# 15_Temp.net
KiCad netlist of a schematic drawn in Altium Designer
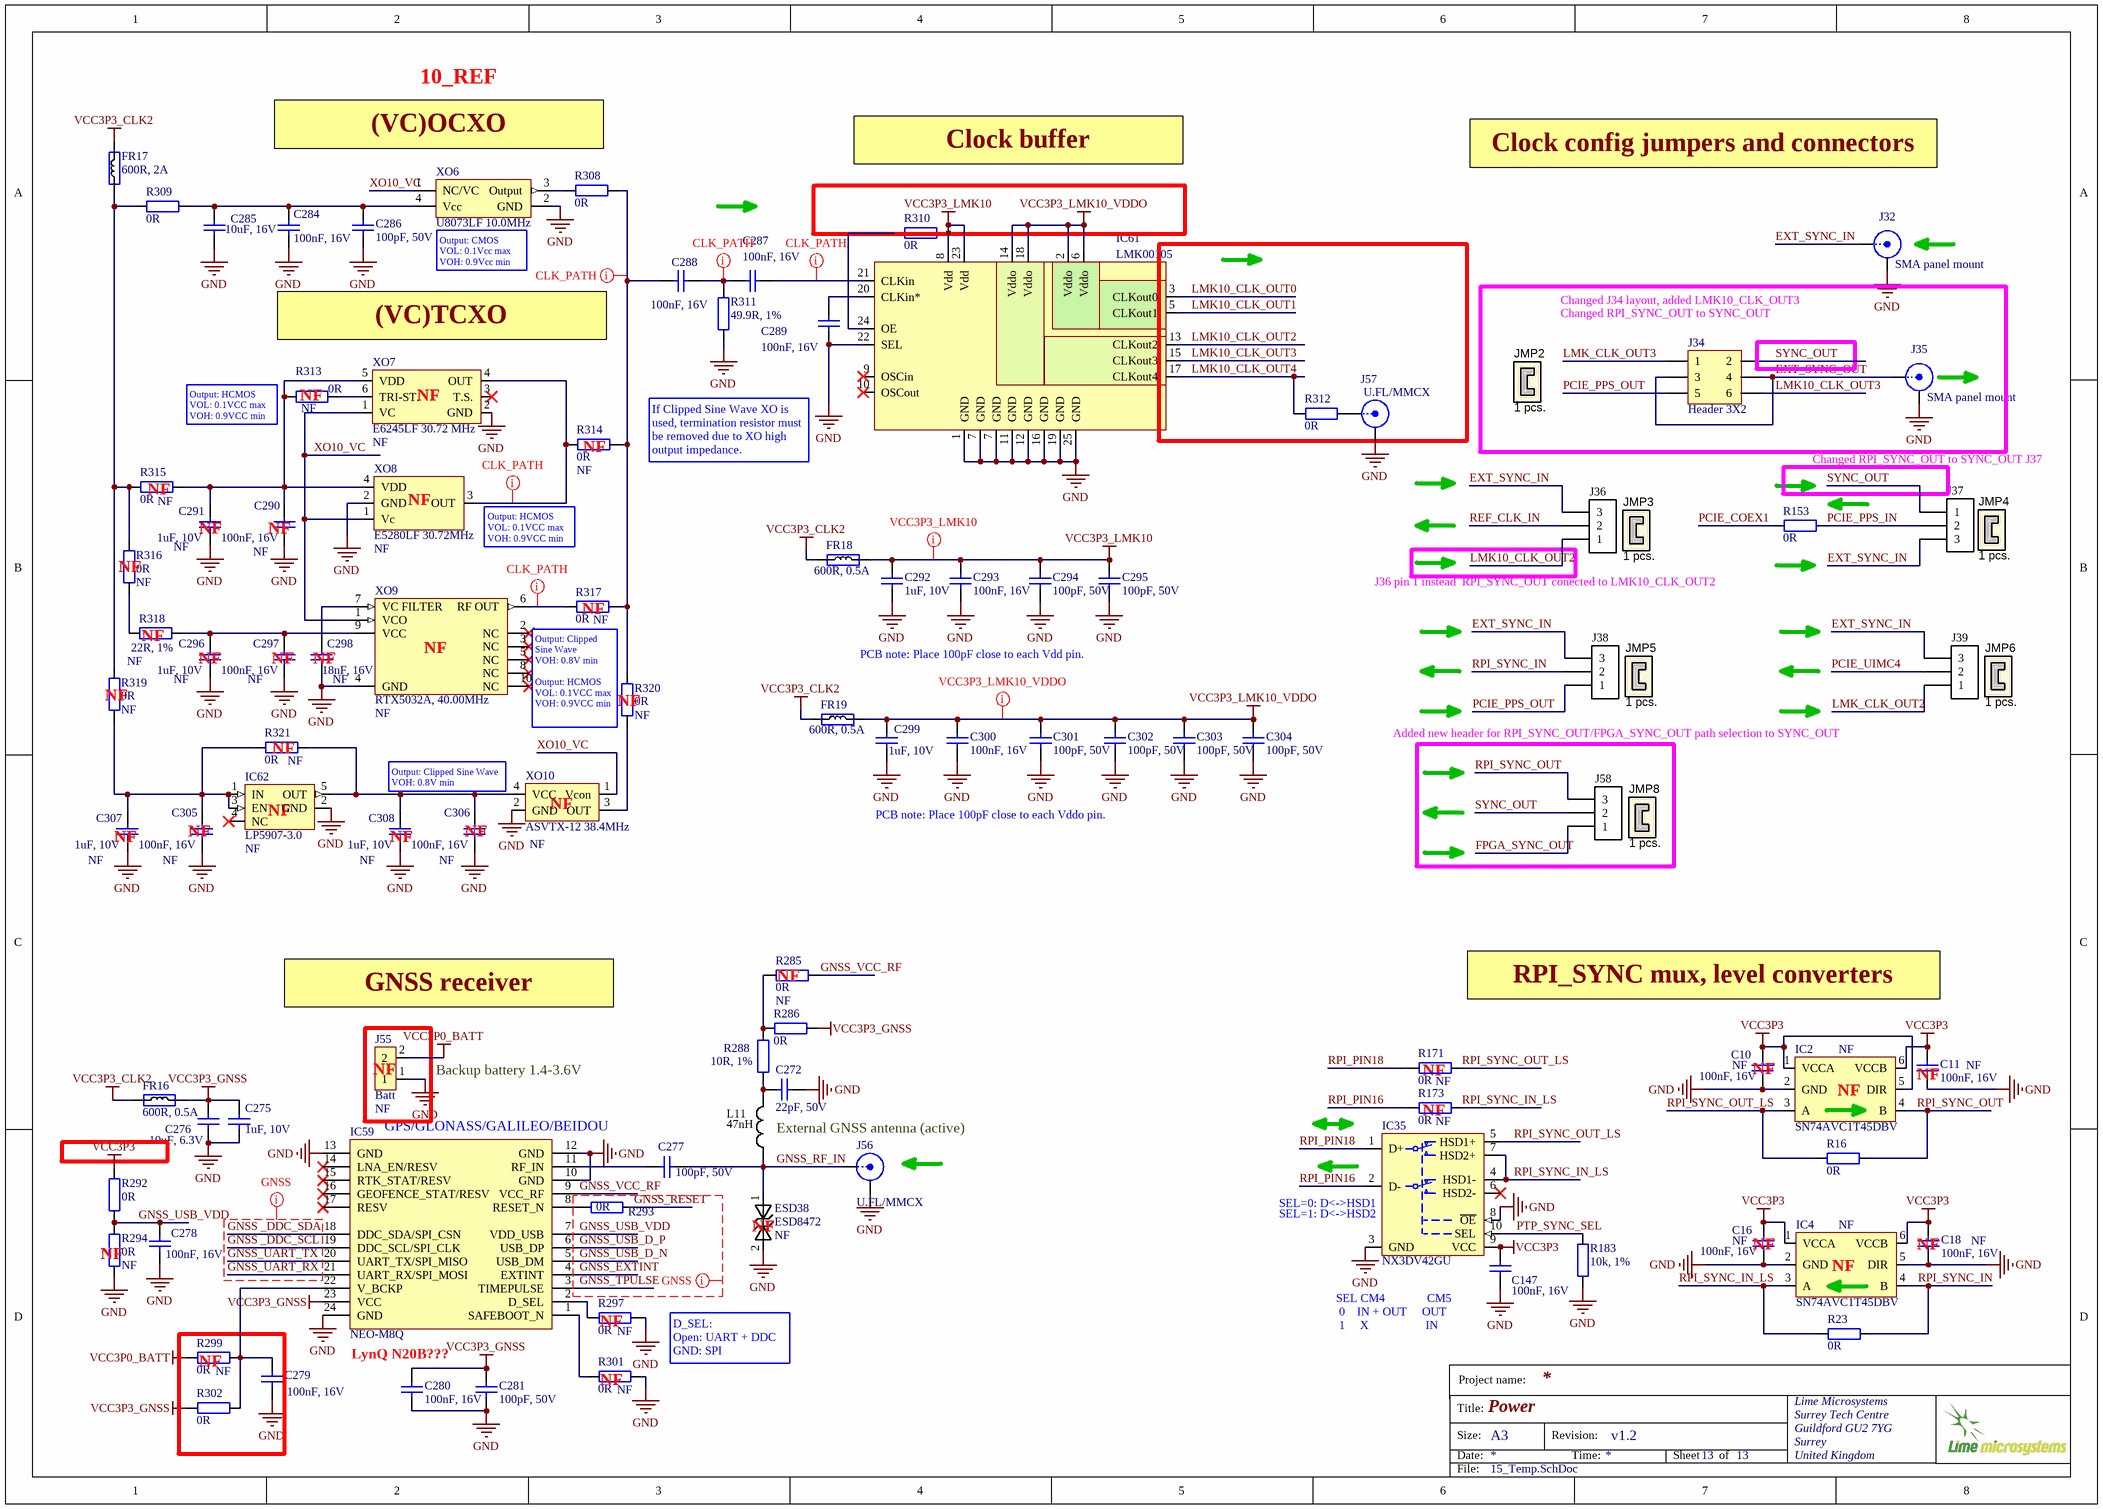
[diagram p0: 15_Temp.SchDoc]

(export (version "E")
  (design (tool "Eeschema 10.0.6"))
  (components
    (comp (ref "C10")
      (value "100nF, 16V")
      (footprint "CAP0402")
      (fields
        (field (name "ASSEMBLY INFO") "NF")
        (field (name "MANUFACTURER") "Murata Electronics")
        (field (name "TOLERANCE") "10 %")
        (field (name "MANUFACTURER PART NUMBER") "GRM155R71C104KA88D")
      )
      (libsource (lib "LimeMicroAltiumLib_schLib") (part "Cap_0402"))
    )
    (comp (ref "C11")
      (value "100nF, 16V")
      (footprint "CAP0402")
      (fields
        (field (name "ASSEMBLY INFO") "NF")
        (field (name "MANUFACTURER") "Murata Electronics")
        (field (name "TOLERANCE") "10 %")
        (field (name "MANUFACTURER PART NUMBER") "GRM155R71C104KA88D")
      )
      (libsource (lib "LimeMicroAltiumLib_schLib") (part "Cap_0402"))
    )
    (comp (ref "C16")
      (value "100nF, 16V")
      (footprint "CAP0402")
      (fields
        (field (name "ASSEMBLY INFO") "NF")
        (field (name "MANUFACTURER") "Murata Electronics")
        (field (name "TOLERANCE") "10 %")
        (field (name "MANUFACTURER PART NUMBER") "GRM155R71C104KA88D")
      )
      (libsource (lib "LimeMicroAltiumLib_schLib") (part "Cap_0402"))
    )
    (comp (ref "C18")
      (value "100nF, 16V")
      (footprint "CAP0402")
      (fields
        (field (name "ASSEMBLY INFO") "NF")
        (field (name "MANUFACTURER") "Murata Electronics")
        (field (name "TOLERANCE") "10 %")
        (field (name "MANUFACTURER PART NUMBER") "GRM155R71C104KA88D")
      )
      (libsource (lib "LimeMicroAltiumLib_schLib") (part "Cap_0402"))
    )
    (comp (ref "C147")
      (value "100nF, 16V")
      (footprint "CAP0402")
      (fields
        (field (name "MANUFACTURER") "Murata Electronics")
        (field (name "TOLERANCE") "10 %")
        (field (name "MANUFACTURER PART NUMBER") "GRM155R71C104KA88D")
      )
      (libsource (lib "LimeMicroAltiumLib_schLib") (part "Cap_0402"))
    )
    (comp (ref "C272")
      (value "22pF, 50V")
      (footprint "CAP0402")
      (fields (field (name "TOLERANCE") "±5%") (field (name "MANUFACTURER") "Yageo"))
      (libsource (lib "LimeMicroAltiumLib_schLib") (part "Cap_0402"))
    )
    (comp (ref "C275")
      (value "1uF, 10V")
      (footprint "CAP0402")
      (description "CAP CER 1UF 10V X5R 0402")
      (fields (field (name "MANUFACTURER") "TDK"))
      (libsource (lib "LimeMicroAltiumLib_schLib") (part "Cap_0402"))
    )
    (comp (ref "C276")
      (value "10uF, 6.3V")
      (footprint "CAP0603")
      (fields (field (name "TOLERANCE") "±20%") (field (name "MANUFACTURER") "Yageo"))
      (libsource (lib "LimeFPGAboard_schLib") (part "Cap_0603"))
    )
    (comp (ref "C277")
      (value "100pF, 50V")
      (footprint "CAP0402")
      (fields (field (name "TOLERANCE") "±5%") (field (name "MANUFACTURER") "Yageo"))
      (libsource (lib "LimeMicroAltiumLib_schLib") (part "Cap_0402"))
    )
    (comp (ref "C278")
      (value "100nF, 16V")
      (footprint "CAP0402")
      (fields
        (field (name "TOLERANCE") "10 %")
        (field (name "MANUFACTURER") "Murata Electronics")
        (field (name "MANUFACTURER PART NUMBER") "GRM155R71C104KA88D")
      )
      (libsource (lib "LimeFPGAboard_schLib") (part "Cap_0603"))
    )
    (comp (ref "C279")
      (value "100nF, 16V")
      (footprint "CAP0402")
      (fields
        (field (name "TOLERANCE") "10 %")
        (field (name "MANUFACTURER") "Murata Electronics")
        (field (name "MANUFACTURER PART NUMBER") "GRM155R71C104KA88D")
      )
      (libsource (lib "LimeFPGAboard_schLib") (part "Cap_0603"))
    )
    (comp (ref "C280")
      (value "100nF, 16V")
      (footprint "CAP0402")
      (fields
        (field (name "MANUFACTURER") "Murata Electronics")
        (field (name "TOLERANCE") "10 %")
        (field (name "MANUFACTURER PART NUMBER") "GRM155R71C104KA88D")
      )
      (libsource (lib "LimeMicroAltiumLib_schLib") (part "Cap_0402"))
    )
    (comp (ref "C281")
      (value "100pF, 50V")
      (footprint "CAP0402")
      (fields (field (name "TOLERANCE") "±5%") (field (name "MANUFACTURER") "Yageo"))
      (libsource (lib "LimeMicroAltiumLib_schLib") (part "Cap_0402"))
    )
    (comp (ref "C284")
      (value "100nF, 16V")
      (footprint "CAP0402")
      (fields
        (field (name "MANUFACTURER") "Murata Electronics")
        (field (name "TOLERANCE") "10 %")
        (field (name "MANUFACTURER PART NUMBER") "GRM155R71C104KA88D")
      )
      (libsource (lib "LimeMicroAltiumLib_schLib") (part "Cap_0402"))
    )
    (comp (ref "C285")
      (value "10uF, 16V")
      (footprint "CAP0603")
      (fields (field (name "MANUFACTURER") "Yageo") (field (name "TOLERANCE") "±20%"))
      (libsource (lib "LimeMicroAltiumLib_schLib") (part "Cap_0603"))
    )
    (comp (ref "C286")
      (value "100pF, 50V")
      (footprint "CAP0402")
      (fields (field (name "TOLERANCE") "±5%") (field (name "MANUFACTURER") "Yageo"))
      (libsource (lib "LimeMicroAltiumLib_schLib") (part "Cap_0402"))
    )
    (comp (ref "C287")
      (value "100nF, 16V")
      (footprint "CAP0402")
      (fields
        (field (name "MANUFACTURER") "Murata Electronics")
        (field (name "TOLERANCE") "10 %")
        (field (name "MANUFACTURER PART NUMBER") "GRM155R71C104KA88D")
      )
      (libsource (lib "LimeMicroAltiumLib_schLib") (part "Cap_0402"))
    )
    (comp (ref "C288")
      (value "100nF, 16V")
      (footprint "CAP0402")
      (fields
        (field (name "MANUFACTURER") "Murata Electronics")
        (field (name "TOLERANCE") "10 %")
        (field (name "MANUFACTURER PART NUMBER") "GRM155R71C104KA88D")
      )
      (libsource (lib "LimeMicroAltiumLib_schLib") (part "Cap_0402"))
    )
    (comp (ref "C289")
      (value "100nF, 16V")
      (footprint "CAP0402")
      (fields
        (field (name "MANUFACTURER") "Murata Electronics")
        (field (name "TOLERANCE") "10 %")
        (field (name "MANUFACTURER PART NUMBER") "GRM155R71C104KA88D")
      )
      (libsource (lib "LimeMicroAltiumLib_schLib") (part "Cap_0402"))
    )
    (comp (ref "C290")
      (value "100nF, 16V")
      (footprint "CAP0402")
      (fields
        (field (name "ASSEMBLY INFO") "NF")
        (field (name "MANUFACTURER") "Murata Electronics")
        (field (name "TOLERANCE") "10 %")
        (field (name "MANUFACTURER PART NUMBER") "GRM155R71C104KA88D")
      )
      (libsource (lib "LimeMicroAltiumLib_schLib") (part "Cap_0402"))
    )
    (comp (ref "C291")
      (value "1uF, 10V")
      (footprint "CAP0402")
      (description "CAP CER 1UF 10V X5R 0402")
      (fields (field (name "ASSEMBLY INFO") "NF") (field (name "MANUFACTURER") "Yageo"))
      (libsource (lib "LimeMicroAltiumLib_schLib") (part "Cap_0402"))
    )
    (comp (ref "C292")
      (value "1uF, 10V")
      (footprint "CAP0402")
      (description "CAP CER 1UF 10V X5R 0402")
      (fields (field (name "MANUFACTURER") "Yageo") (field (name "TOLERANCE") "±20%"))
      (libsource (lib "LimeMicroAltiumLib_schLib") (part "Cap_0402"))
    )
    (comp (ref "C293")
      (value "100nF, 16V")
      (footprint "CAP0402")
      (fields
        (field (name "MANUFACTURER") "Murata Electronics")
        (field (name "TOLERANCE") "10 %")
        (field (name "MANUFACTURER PART NUMBER") "GRM155R71C104KA88D")
      )
      (libsource (lib "LimeMicroAltiumLib_schLib") (part "Cap_0402"))
    )
    (comp (ref "C294")
      (value "100pF, 50V")
      (footprint "CAP0402")
      (fields (field (name "MANUFACTURER") "Yageo") (field (name "TOLERANCE") "±5%"))
      (libsource (lib "LimeMicroAltiumLib_schLib") (part "Cap_0402"))
    )
    (comp (ref "C295")
      (value "100pF, 50V")
      (footprint "CAP0402")
      (fields (field (name "MANUFACTURER") "Yageo") (field (name "TOLERANCE") "±5%"))
      (libsource (lib "LimeMicroAltiumLib_schLib") (part "Cap_0402"))
    )
    (comp (ref "C296")
      (value "1uF, 10V")
      (footprint "CAP0402")
      (description "CAP CER 1UF 10V X5R 0402")
      (fields (field (name "ASSEMBLY INFO") "NF") (field (name "MANUFACTURER") "Yageo"))
      (libsource (lib "LimeMicroAltiumLib_schLib") (part "Cap_0402"))
    )
    (comp (ref "C297")
      (value "100nF, 16V")
      (footprint "CAP0402")
      (fields
        (field (name "ASSEMBLY INFO") "NF")
        (field (name "MANUFACTURER") "Murata Electronics")
        (field (name "TOLERANCE") "10 %")
        (field (name "MANUFACTURER PART NUMBER") "GRM155R71C104KA88D")
      )
      (libsource (lib "LimeMicroAltiumLib_schLib") (part "Cap_0402"))
    )
    (comp (ref "C298")
      (value "18nF, 16V")
      (footprint "CAP0402")
      (fields
        (field (name "ASSEMBLY INFO") "NF")
        (field (name "MANUFACTURER") "Yageo")
        (field (name "TOLERANCE") "±10%")
      )
      (libsource (lib "LimeMicroAltiumLib_schLib") (part "Cap_0402"))
    )
    (comp (ref "C299")
      (value "1uF, 10V")
      (footprint "CAP0402")
      (description "CAP CER 1UF 10V X5R 0402")
      (fields (field (name "MANUFACTURER") "Yageo") (field (name "TOLERANCE") "±20%"))
      (libsource (lib "LimeMicroAltiumLib_schLib") (part "Cap_0402"))
    )
    (comp (ref "C300")
      (value "100nF, 16V")
      (footprint "CAP0402")
      (fields
        (field (name "MANUFACTURER") "Murata Electronics")
        (field (name "TOLERANCE") "10 %")
        (field (name "MANUFACTURER PART NUMBER") "GRM155R71C104KA88D")
      )
      (libsource (lib "LimeMicroAltiumLib_schLib") (part "Cap_0402"))
    )
    (comp (ref "C301")
      (value "100pF, 50V")
      (footprint "CAP0402")
      (fields (field (name "MANUFACTURER") "Yageo") (field (name "TOLERANCE") "±5%"))
      (libsource (lib "LimeMicroAltiumLib_schLib") (part "Cap_0402"))
    )
    (comp (ref "C302")
      (value "100pF, 50V")
      (footprint "CAP0402")
      (fields (field (name "MANUFACTURER") "Yageo") (field (name "TOLERANCE") "±5%"))
      (libsource (lib "LimeMicroAltiumLib_schLib") (part "Cap_0402"))
    )
    (comp (ref "C303")
      (value "100pF, 50V")
      (footprint "CAP0402")
      (fields (field (name "MANUFACTURER") "Yageo") (field (name "TOLERANCE") "±5%"))
      (libsource (lib "LimeMicroAltiumLib_schLib") (part "Cap_0402"))
    )
    (comp (ref "C304")
      (value "100pF, 50V")
      (footprint "CAP0402")
      (fields (field (name "MANUFACTURER") "Yageo") (field (name "TOLERANCE") "±5%"))
      (libsource (lib "LimeMicroAltiumLib_schLib") (part "Cap_0402"))
    )
    (comp (ref "C305")
      (value "100nF, 16V")
      (footprint "CAP0402")
      (fields
        (field (name "ASSEMBLY INFO") "NF")
        (field (name "MANUFACTURER") "Murata Electronics")
        (field (name "TOLERANCE") "10 %")
        (field (name "MANUFACTURER PART NUMBER") "GRM155R71C104KA88D")
      )
      (libsource (lib "") (part "Cap_0402_1"))
    )
    (comp (ref "C306")
      (value "100nF, 16V")
      (footprint "CAP0402")
      (fields
        (field (name "ASSEMBLY INFO") "NF")
        (field (name "MANUFACTURER") "Murata Electronics")
        (field (name "TOLERANCE") "10 %")
        (field (name "MANUFACTURER PART NUMBER") "GRM155R71C104KA88D")
      )
      (libsource (lib "") (part "Cap_0402_1"))
    )
    (comp (ref "C307")
      (value "1uF, 10V")
      (footprint "CAP0402")
      (fields (field (name "ASSEMBLY INFO") "NF") (field (name "MANUFACTURER") "Yageo"))
      (libsource (lib "") (part "Cap_0402_1"))
    )
    (comp (ref "C308")
      (value "1uF, 10V")
      (footprint "CAP0402")
      (fields (field (name "ASSEMBLY INFO") "NF") (field (name "MANUFACTURER") "Yageo"))
      (libsource (lib "") (part "Cap_0402_1"))
    )
    (comp (ref "ESD38")
      (value "ESD8472")
      (footprint "ESD8472_X3DFN2")
      (fields
        (field (name "MANUFACTURER") "ON Semiconductor")
        (field (name "MANUFACTURER PART NUMBER") "ESD8472MUT5G")
        (field (name "ASSEMBLY INFO") "NF")
      )
      (libsource (lib "LimeMicroAltiumLib_schLib") (part "ESD8472"))
    )
    (comp (ref "FR16")
      (value "600R, 0.5A")
      (footprint "RES0402")
      (fields
        (field (name "MANUFACTURER") "Murata")
        (field (name "TOLERANCE") "25%")
        (field (name "Comment") "Ferrite")
      )
      (libsource (lib "LimeMicroAltiumLib_schLib") (part "Ferrite"))
    )
    (comp (ref "FR17")
      (value "600R, 2A")
      (footprint "RES0805")
      (fields (field (name "MANUFACTURER") "TDK Corporation"))
      (libsource (lib "LimeFPGAboard_schLib") (part "Ferrite"))
    )
    (comp (ref "FR18")
      (value "600R, 0.5A")
      (footprint "RES0402")
      (fields (field (name "MANUFACTURER") "Murata") (field (name "TOLERANCE") "25%"))
      (libsource (lib "LimeMicroAltiumLib_schLib") (part "Ferrite"))
    )
    (comp (ref "FR19")
      (value "600R, 0.5A")
      (footprint "RES0402")
      (fields (field (name "MANUFACTURER") "Murata") (field (name "TOLERANCE") "25%"))
      (libsource (lib "LimeMicroAltiumLib_schLib") (part "Ferrite"))
    )
    (comp (ref "IC2")
      (value "SN74AVC1T45DBV")
      (footprint "SOT23-6")
      (fields (field (name "ASSEMBLY INFO") "NF") (field (name "MANUFACTURER") "Texas Instruments"))
      (libsource (lib "LimeMicroAltiumLib_schLib_r04") (part "SN74AVC1T45DBV"))
    )
    (comp (ref "IC4")
      (value "SN74AVC1T45DBV")
      (footprint "SOT23-6")
      (fields (field (name "ASSEMBLY INFO") "NF") (field (name "MANUFACTURER") "Texas Instruments"))
      (libsource (lib "LimeMicroAltiumLib_schLib_r04") (part "SN74AVC1T45DBV"))
    )
    (comp (ref "IC35")
      (value "NX3DV42GU")
      (footprint "FSUSB42UMX")
      (fields (field (name "MANUFACTURER") "NXP Semiconductors"))
      (libsource (lib "LimeMicroAltiumLib_schLib_r01") (part "FSUSB42UMX"))
    )
    (comp (ref "IC59")
      (value "NEO-M8Q")
      (footprint "NEO-7M/8M")
      (description "GNSS engine for GPS/QZSS, GLONASS")
      (fields (field (name "MANUFACTURER") "U-blox"))
      (libsource (lib "LimeMicroAltiumLib_schLib") (part "NEO-M8P_M8M"))
    )
    (comp (ref "IC61")
      (value "LMK00105")
      (footprint "LMK00105SQ")
      (fields (field (name "MANUFACTURER") "Texas Instruments"))
      (libsource (lib "LimeMicroAltiumLib_schLib") (part "LMK00105"))
    )
    (comp (ref "IC62")
      (value "LP5907-3.0")
      (footprint "SOT23-5")
      (fields (field (name "MANUFACTURER") "Texas Instruments") (field (name "ASSEMBLY INFO") "NF"))
      (libsource (lib "LimeMicroAltiumLib_schLib_r01") (part "LP5907"))
    )
    (comp (ref "J32")
      (value "SMA panel mount")
      (footprint "SMA_connector_side")
      (description "CONN SMA JACK STR 50OHM EDGE MNT")
      (fields (field (name "MANUFACTURER") "Linx"))
      (libsource (lib "LimeMicroAltiumLib_schLib") (part "RF_IF_connector"))
    )
    (comp (ref "J34")
      (value "Header 3X2")
      (footprint "Header3x2")
      (description "Header, 2-Pin, Dual row")
      (fields
        (field (name "MANUFACTURER PART NUMBER") "PH2-06-UA")
        (field (name "MANUFACTURER") "Adam Equipment")
      )
      (libsource (lib "LimeMicroAltiumLib_schLib_r01") (part "Header 3X2"))
    )
    (comp (ref "J35")
      (value "SMA panel mount")
      (footprint "SMA_connector_side")
      (description "CONN SMA JACK STR 50OHM EDGE MNT")
      (fields (field (name "MANUFACTURER") "Linx"))
      (libsource (lib "LimeMicroAltiumLib_schLib") (part "RF_IF_connector"))
    )
    (comp (ref "J36")
      (value "Header 3x1 pin")
      (footprint "HDR_1x3")
      (description "Header, 3-pin")
      (fields
        (field (name "MANUFACTURER PART NUMBER") "61300311121")
        (field (name "MANUFACTURER") "Wurth Electronics")
      )
      (libsource (lib "LimeMicroAltiumLib_schLib_r04") (part "Header3P"))
    )
    (comp (ref "J37")
      (value "Header 3x1 pin")
      (footprint "HDR_1x3")
      (description "Header, 3-pin")
      (fields
        (field (name "MANUFACTURER PART NUMBER") "61300311121")
        (field (name "MANUFACTURER") "Wurth Electronics")
      )
      (libsource (lib "") (part "Header3P_1"))
    )
    (comp (ref "J38")
      (value "Header 3x1 pin")
      (footprint "HDR_1x3")
      (description "Header, 3-pin")
      (fields
        (field (name "MANUFACTURER PART NUMBER") "61300311121")
        (field (name "MANUFACTURER") "Wurth Electronics")
      )
      (libsource (lib "LimeMicroAltiumLib_schLib_r04") (part "Header3P"))
    )
    (comp (ref "J39")
      (value "Header 3x1 pin")
      (footprint "HDR_1x3")
      (description "Header, 3-pin")
      (fields
        (field (name "MANUFACTURER PART NUMBER") "61300311121")
        (field (name "MANUFACTURER") "Wurth Electronics")
      )
      (libsource (lib "LimeMicroAltiumLib_schLib_r04") (part "Header3P"))
    )
    (comp (ref "J55")
      (value "Batt")
      (footprint "HDR_1x2")
      (fields (field (name "ASSEMBLY INFO") "NF") (field (name "MANUFACTURER") "3M"))
      (libsource (lib "LimeFPGAboard_schLib") (part "Jumper"))
    )
    (comp (ref "J56")
      (value "U.FL/MMCX")
      (footprint "MMCX_UFL_conn_u")
      (description "CONN UMC RCPT STR 50 OHM SMD")
      (fields (field (name "MANUFACTURER") "Molex, LLC"))
      (libsource (lib "") (part "RF_IF_connector_1"))
    )
    (comp (ref "J57")
      (value "U.FL/MMCX")
      (footprint "MMCX_UFL_conn_u")
      (description "CONN UMC RCPT STR 50 OHM SMD")
      (fields (field (name "MANUFACTURER") "Molex, LLC"))
      (libsource (lib "") (part "RF_IF_connector_1"))
    )
    (comp (ref "J58")
      (value "Header 3x1 pin")
      (footprint "HDR_1x3")
      (description "Header, 3-pin")
      (fields
        (field (name "MANUFACTURER PART NUMBER") "61300311121")
        (field (name "MANUFACTURER") "Wurth Electronics")
      )
      (libsource (lib "LimeMicroAltiumLib_schLib_r04") (part "Header3P"))
    )
    (comp (ref "JMP2")
      (value "1 pcs.")
      (description "Shorting Jumper, 2-position, 1.27mm pitch")
      (fields (field (name "MANUFACTURER") "Sullins"))
      (libsource (lib "LimeMicroAltiumLib_schLib") (part "JUMP_2P_CONN_HEADER"))
    )
    (comp (ref "JMP3")
      (value "1 pcs.")
      (description "Shorting Jumper, 2-position, 1.27mm pitch")
      (fields (field (name "MANUFACTURER") "Sullins"))
      (libsource (lib "LimeMicroAltiumLib_schLib") (part "JUMP_2P_CONN_HEADER"))
    )
    (comp (ref "JMP4")
      (value "1 pcs.")
      (description "Shorting Jumper, 2-position, 1.27mm pitch")
      (fields (field (name "MANUFACTURER") "Sullins"))
      (libsource (lib "LimeMicroAltiumLib_schLib") (part "JUMP_2P_CONN_HEADER"))
    )
    (comp (ref "JMP5")
      (value "1 pcs.")
      (description "Shorting Jumper, 2-position, 1.27mm pitch")
      (fields (field (name "MANUFACTURER") "Sullins"))
      (libsource (lib "LimeMicroAltiumLib_schLib") (part "JUMP_2P_CONN_HEADER"))
    )
    (comp (ref "JMP6")
      (value "1 pcs.")
      (description "Shorting Jumper, 2-position, 1.27mm pitch")
      (fields (field (name "MANUFACTURER") "Sullins"))
      (libsource (lib "LimeMicroAltiumLib_schLib") (part "JUMP_2P_CONN_HEADER"))
    )
    (comp (ref "JMP8")
      (value "1 pcs.")
      (description "Shorting Jumper, 2-position, 1.27mm pitch")
      (fields (field (name "MANUFACTURER") "Sullins"))
      (libsource (lib "LimeMicroAltiumLib_schLib") (part "JUMP_2P_CONN_HEADER"))
    )
    (comp (ref "L11")
      (value "47nH")
      (footprint "RES0402")
      (fields
        (field (name "MANUFACTURER") "COILCRAFT")
        (field (name "MANUFACTURER PART NUMBER") "0402HP-47NXJLU")
      )
      (libsource (lib "LimeMicroAltiumLib_schLib") (part "Inductor_0603"))
    )
    (comp (ref "R16")
      (value "0R")
      (footprint "RES0402")
      (fields (field (name "MANUFACTURER") "Yageo") (field (name "TOLERANCE") "Jumper"))
      (libsource (lib "LimeFPGAboard_schLib") (part "Res_0402"))
    )
    (comp (ref "R23")
      (value "0R")
      (footprint "RES0402")
      (fields (field (name "MANUFACTURER") "Yageo") (field (name "TOLERANCE") "Jumper"))
      (libsource (lib "LimeFPGAboard_schLib") (part "Res_0402"))
    )
    (comp (ref "R153")
      (value "0R")
      (footprint "RES0402")
      (fields (field (name "MANUFACTURER") "Yageo") (field (name "TOLERANCE") "Jumper"))
      (libsource (lib "") (part "Res_0402_1"))
    )
    (comp (ref "R171")
      (value "0R")
      (footprint "RES0402")
      (fields
        (field (name "ASSEMBLY INFO") "NF")
        (field (name "MANUFACTURER") "Yageo")
        (field (name "TOLERANCE") "Jumper")
      )
      (libsource (lib "") (part "Res_0402_1"))
    )
    (comp (ref "R173")
      (value "0R")
      (footprint "RES0402")
      (fields
        (field (name "ASSEMBLY INFO") "NF")
        (field (name "MANUFACTURER") "Yageo")
        (field (name "TOLERANCE") "Jumper")
      )
      (libsource (lib "") (part "Res_0402_1"))
    )
    (comp (ref "R183")
      (value "10k, 1%")
      (footprint "RES0402")
      (fields (field (name "MANUFACTURER") "Yageo") (field (name "TOLERANCE") "±1%"))
      (libsource (lib "LimeMicroAltiumLib_schLib") (part "Res_0402"))
    )
    (comp (ref "R285")
      (value "0R")
      (footprint "RES0402")
      (fields
        (field (name "ASSEMBLY INFO") "NF")
        (field (name "MANUFACTURER") "Yageo")
        (field (name "TOLERANCE") "Jumper")
      )
      (libsource (lib "LimeMicroAltiumLib_schLib") (part "Res_0402"))
    )
    (comp (ref "R286")
      (value "0R")
      (footprint "RES0402")
      (fields (field (name "MANUFACTURER") "Yageo") (field (name "TOLERANCE") "Jumper"))
      (libsource (lib "LimeMicroAltiumLib_schLib") (part "Res_0402"))
    )
    (comp (ref "R288")
      (value "10R, 1%")
      (footprint "RES0402")
      (fields (field (name "MANUFACTURER") "Stackpole Electronics") (field (name "TOLERANCE") "1%"))
      (libsource (lib "LimeMicroAltiumLib_schLib") (part "Res_0402"))
    )
    (comp (ref "R292")
      (value "0R")
      (footprint "RES0402")
      (fields (field (name "MANUFACTURER") "Yageo") (field (name "TOLERANCE") "Jumper"))
      (libsource (lib "LimeMicroAltiumLib_schLib") (part "Res_0402"))
    )
    (comp (ref "R293")
      (value "0R")
      (footprint "RES0402")
      (fields (field (name "MANUFACTURER") "Yageo") (field (name "TOLERANCE") "Jumper"))
      (libsource (lib "LimeMicroAltiumLib_schLib") (part "Res_0402"))
    )
    (comp (ref "R294")
      (value "0R")
      (footprint "RES0402")
      (fields
        (field (name "ASSEMBLY INFO") "NF")
        (field (name "MANUFACTURER") "Yageo")
        (field (name "TOLERANCE") "Jumper")
      )
      (libsource (lib "LimeMicroAltiumLib_schLib") (part "Res_0402"))
    )
    (comp (ref "R297")
      (value "0R")
      (footprint "RES0402")
      (fields
        (field (name "ASSEMBLY INFO") "NF")
        (field (name "MANUFACTURER") "Yageo")
        (field (name "TOLERANCE") "Jumper")
      )
      (libsource (lib "LimeMicroAltiumLib_schLib") (part "Res_0402"))
    )
    (comp (ref "R299")
      (value "0R")
      (footprint "RES0402")
      (fields
        (field (name "ASSEMBLY INFO") "NF")
        (field (name "MANUFACTURER") "Yageo")
        (field (name "TOLERANCE") "Jumper")
      )
      (libsource (lib "LimeMicroAltiumLib_schLib") (part "Res_0402"))
    )
    (comp (ref "R301")
      (value "0R")
      (footprint "RES0402")
      (fields
        (field (name "ASSEMBLY INFO") "NF")
        (field (name "MANUFACTURER") "Yageo")
        (field (name "TOLERANCE") "Jumper")
      )
      (libsource (lib "LimeMicroAltiumLib_schLib") (part "Res_0402"))
    )
    (comp (ref "R302")
      (value "0R")
      (footprint "RES0402")
      (fields (field (name "MANUFACTURER") "Yageo") (field (name "TOLERANCE") "Jumper"))
      (libsource (lib "LimeMicroAltiumLib_schLib") (part "Res_0402"))
    )
    (comp (ref "R308")
      (value "0R")
      (footprint "RES0402_v2")
      (fields (field (name "MANUFACTURER") "Yageo") (field (name "TOLERANCE") "Jumper"))
      (libsource (lib "LimeMicroAltiumLib_schLib") (part "Res_0402"))
    )
    (comp (ref "R309")
      (value "0R")
      (footprint "RES0402")
      (fields (field (name "MANUFACTURER") "Yageo") (field (name "TOLERANCE") "Jumper"))
      (libsource (lib "LimeMicroAltiumLib_schLib") (part "Res_0402"))
    )
    (comp (ref "R310")
      (value "0R")
      (footprint "RES0402")
      (fields (field (name "MANUFACTURER") "Yageo") (field (name "TOLERANCE") "Jumper"))
      (libsource (lib "LimeMicroAltiumLib_schLib") (part "Res_0402"))
    )
    (comp (ref "R311")
      (value "49.9R, 1%")
      (footprint "RES0402")
      (fields
        (field (name "TOLERANCE") "±1%")
        (field (name "MANUFACTURER") "Samsung Electro-Mechanics America, Inc.")
      )
      (libsource (lib "LimeMicroAltiumLib_schLib") (part "Res_0402"))
    )
    (comp (ref "R312")
      (value "0R")
      (footprint "RES0402")
      (fields (field (name "MANUFACTURER") "Yageo") (field (name "TOLERANCE") "Jumper"))
      (libsource (lib "") (part "Res_0402_1"))
    )
    (comp (ref "R313")
      (value "0R")
      (footprint "RES0402")
      (fields
        (field (name "ASSEMBLY INFO") "NF")
        (field (name "MANUFACTURER") "Yageo")
        (field (name "TOLERANCE") "Jumper")
      )
      (libsource (lib "LimeMicroAltiumLib_schLib") (part "Res_0402"))
    )
    (comp (ref "R314")
      (value "0R")
      (footprint "RES0402_v2")
      (fields
        (field (name "ASSEMBLY INFO") "NF")
        (field (name "MANUFACTURER") "Yageo")
        (field (name "TOLERANCE") "Jumper")
      )
      (libsource (lib "LimeMicroAltiumLib_schLib") (part "Res_0402"))
    )
    (comp (ref "R315")
      (value "0R")
      (footprint "RES0402")
      (fields
        (field (name "MANUFACTURER") "Yageo")
        (field (name "TOLERANCE") "Jumper")
        (field (name "ASSEMBLY INFO") "NF")
      )
      (libsource (lib "LimeMicroAltiumLib_schLib") (part "Res_0402"))
    )
    (comp (ref "R316")
      (value "0R")
      (footprint "RES0402")
      (fields
        (field (name "ASSEMBLY INFO") "NF")
        (field (name "MANUFACTURER") "Yageo")
        (field (name "TOLERANCE") "Jumper")
      )
      (libsource (lib "LimeMicroAltiumLib_schLib") (part "Res_0402"))
    )
    (comp (ref "R317")
      (value "0R")
      (footprint "RES0402_v2")
      (fields
        (field (name "ASSEMBLY INFO") "NF")
        (field (name "MANUFACTURER") "Yageo")
        (field (name "TOLERANCE") "Jumper")
      )
      (libsource (lib "LimeMicroAltiumLib_schLib") (part "Res_0402"))
    )
    (comp (ref "R318")
      (value "22R, 1%")
      (footprint "RES0402")
      (fields
        (field (name "TOLERANCE") "±1%")
        (field (name "MANUFACTURER") "Yageo")
        (field (name "ASSEMBLY INFO") "NF")
      )
      (libsource (lib "LimeFPGAboard_schLib") (part "Res_0402"))
    )
    (comp (ref "R319")
      (value "0R")
      (footprint "RES0402")
      (fields
        (field (name "MANUFACTURER") "Yageo")
        (field (name "TOLERANCE") "Jumper")
        (field (name "ASSEMBLY INFO") "NF")
      )
      (libsource (lib "") (part "Res_0402_1"))
    )
    (comp (ref "R320")
      (value "0R")
      (footprint "RES0402_v2")
      (fields
        (field (name "ASSEMBLY INFO") "NF")
        (field (name "MANUFACTURER") "Yageo")
        (field (name "TOLERANCE") "Jumper")
      )
      (libsource (lib "") (part "Res_0402_1"))
    )
    (comp (ref "R321")
      (value "0R")
      (footprint "RES0402")
      (fields
        (field (name "MANUFACTURER") "Yageo")
        (field (name "TOLERANCE") "Jumper")
        (field (name "ASSEMBLY INFO") "NF")
      )
      (libsource (lib "") (part "Res_0402_1"))
    )
    (comp (ref "XO6")
      (value "U8073LF 10.0MHz")
      (footprint "AOCJYR-10.000MHz")
      (fields (field (name "MANUFACTURER") "Rakon"))
      (libsource (lib "LimeMicroAltiumLib_schLib") (part "AOCJYR-10.000MHz"))
    )
    (comp (ref "XO7")
      (value "E6245LF 30.72 MHz")
      (footprint "RAKON_RPT7050A")
      (fields (field (name "ASSEMBLY INFO") "NF") (field (name "MANUFACTURER") "Rakon"))
      (libsource (lib "LimeMicroAltiumLib_schLib") (part "RPT7050A"))
    )
    (comp (ref "XO8")
      (value "E5280LF 30.72MHz")
      (footprint "RAKON_TXCO")
      (fields (field (name "ASSEMBLY INFO") "NF") (field (name "MANUFACTURER") "Rakon"))
      (libsource (lib "LimeMicroAltiumLib_schLib") (part "TXCO"))
    )
    (comp (ref "XO9")
      (value "RTX5032A, 40.00MHz")
      (footprint "RAKON_RTX5032A")
      (fields (field (name "ASSEMBLY INFO") "NF") (field (name "MANUFACTURER") "Rakon"))
      (libsource (lib "LimeMicroAltiumLib_schLib") (part "Rakon_RTX5032A"))
    )
    (comp (ref "XO10")
      (value "ASVTX-12 38.4MHz")
      (footprint "CRYSTAL_4-LCC_2P5x2P0")
      (description "Oscillator Crystal")
      (fields (field (name "MANUFACTURER") "Abracon") (field (name "ASSEMBLY INFO") "NF"))
      (libsource (lib "LimeMicroAltiumLib_schLib_r01") (part "ASVTX-12-A-38.400MHZ-H10-T_CRYSTAL"))
    )
  )
  (nets
    (net (code "1") (name "/EXT_SYNC_IN") (class "Default")
      (node (ref "J32") (pin "1") (pinfunction "X_1") (pintype "passive"))
      (node (ref "J36") (pin "3") (pinfunction "3_3") (pintype "passive"))
      (node (ref "J37") (pin "3") (pinfunction "3_3") (pintype "passive"))
      (node (ref "J38") (pin "3") (pinfunction "3_3") (pintype "passive"))
      (node (ref "J39") (pin "3") (pinfunction "3_3") (pintype "passive"))
    )
    (net (code "2") (name "/EXT_SYNC_OUT") (class "Default")
      (node (ref "J34") (pin "3") (pinfunction "3_3") (pintype "passive"))
      (node (ref "J34") (pin "4") (pinfunction "4_4") (pintype "passive"))
      (node (ref "J35") (pin "1") (pinfunction "X_1") (pintype "passive"))
    )
    (net (code "3") (name "/FPGA_SYNC_OUT") (class "Default")
      (node (ref "J58") (pin "1") (pinfunction "1_1") (pintype "passive"))
    )
    (net (code "4") (name "/GNSS _DDC_SCL") (class "Default")
      (node (ref "IC59") (pin "19") (pinfunction "DDC_SCL/SPI_CLK_19") (pintype "passive"))
    )
    (net (code "5") (name "/GNSS _DDC_SDA") (class "Default")
      (node (ref "IC59") (pin "18") (pinfunction "DDC_SDA/SPI_CSN_18") (pintype "passive"))
    )
    (net (code "6") (name "/GNSS_EXTINT") (class "Default")
      (node (ref "IC59") (pin "4") (pinfunction "EXTINT_4") (pintype "passive"))
    )
    (net (code "7") (name "/GNSS_RESET") (class "Default")
      (node (ref "R293") (pin "1") (pinfunction "1_1") (pintype "passive"))
    )
    (net (code "8") (name "/GNSS_RF_IN") (class "Default")
      (node (ref "C277") (pin "1") (pinfunction "1_1") (pintype "passive"))
      (node (ref "ESD38") (pin "1") (pinfunction "1_1") (pintype "passive"))
      (node (ref "J56") (pin "1") (pinfunction "X_1") (pintype "passive"))
      (node (ref "L11") (pin "1") (pinfunction "1_1") (pintype "passive"))
    )
    (net (code "9") (name "/GNSS_TPULSE") (class "Default")
      (node (ref "IC59") (pin "3") (pinfunction "TIMEPULSE_3") (pintype "passive"))
    )
    (net (code "10") (name "/GNSS_UART_RX") (class "Default")
      (node (ref "IC59") (pin "21") (pinfunction "UART_RX/SPI_MOSI_21") (pintype "passive"))
    )
    (net (code "11") (name "/GNSS_UART_TX") (class "Default")
      (node (ref "IC59") (pin "20") (pinfunction "UART_TX/SPI_MISO_20") (pintype "passive"))
    )
    (net (code "12") (name "/GNSS_USB_D_N") (class "Default")
      (node (ref "IC59") (pin "5") (pinfunction "USB_DM_5") (pintype "passive"))
    )
    (net (code "13") (name "/GNSS_USB_D_P") (class "Default")
      (node (ref "IC59") (pin "6") (pinfunction "USB_DP_6") (pintype "passive"))
    )
    (net (code "14") (name "/GNSS_USB_VDD") (class "Default")
      (node (ref "C278") (pin "1") (pinfunction "1_1") (pintype "passive"))
      (node (ref "IC59") (pin "7") (pinfunction "VDD_USB_7") (pintype "passive"))
      (node (ref "R292") (pin "2") (pinfunction "2_2") (pintype "passive"))
      (node (ref "R294") (pin "2") (pinfunction "2_2") (pintype "passive"))
    )
    (net (code "15") (name "/GNSS_VCC_RF") (class "Default")
      (node (ref "IC59") (pin "9") (pinfunction "VCC_RF_9") (pintype "passive"))
      (node (ref "R285") (pin "2") (pinfunction "2_2") (pintype "passive"))
    )
    (net (code "16") (name "/LMK10_CLK_OUT0") (class "Default")
      (node (ref "IC61") (pin "3") (pinfunction "CLKout0_3") (pintype "passive"))
    )
    (net (code "17") (name "/LMK10_CLK_OUT1") (class "Default")
      (node (ref "IC61") (pin "5") (pinfunction "CLKout1_5") (pintype "passive"))
    )
    (net (code "18") (name "/LMK10_CLK_OUT2") (class "Default")
      (node (ref "IC61") (pin "13") (pinfunction "CLKout2_13") (pintype "passive"))
      (node (ref "J36") (pin "1") (pinfunction "1_1") (pintype "passive"))
    )
    (net (code "19") (name "/LMK10_CLK_OUT3") (class "Default")
      (node (ref "IC61") (pin "15") (pinfunction "CLKout3_15") (pintype "passive"))
      (node (ref "J34") (pin "6") (pinfunction "6_6") (pintype "passive"))
    )
    (net (code "20") (name "/LMK10_CLK_OUT4") (class "Default")
      (node (ref "IC61") (pin "17") (pinfunction "CLKout4_17") (pintype "passive"))
      (node (ref "R312") (pin "2") (pinfunction "2_2") (pintype "passive"))
    )
    (net (code "21") (name "/LMK_CLK_OUT2") (class "Default")
      (node (ref "J39") (pin "1") (pinfunction "1_1") (pintype "passive"))
    )
    (net (code "22") (name "/LMK_CLK_OUT3") (class "Default")
      (node (ref "J34") (pin "1") (pinfunction "1_1") (pintype "passive"))
    )
    (net (code "23") (name "/PCIE_COEX1") (class "Default")
      (node (ref "R153") (pin "2") (pinfunction "2_2") (pintype "passive"))
    )
    (net (code "25") (name "/PCIE_PPS_IN") (class "Default")
      (node (ref "J37") (pin "2") (pinfunction "2_2") (pintype "passive"))
      (node (ref "R153") (pin "1") (pinfunction "1_1") (pintype "passive"))
    )
    (net (code "26") (name "/PCIE_PPS_OUT") (class "Default")
      (node (ref "J34") (pin "5") (pinfunction "5_5") (pintype "passive"))
      (node (ref "J38") (pin "1") (pinfunction "1_1") (pintype "passive"))
    )
    (net (code "27") (name "/PCIE_UIMC4") (class "Default")
      (node (ref "J39") (pin "2") (pinfunction "2_2") (pintype "passive"))
    )
    (net (code "28") (name "/PTP_SYNC_SEL") (class "Default")
      (node (ref "IC35") (pin "10") (pinfunction "SEL_10") (pintype "input"))
      (node (ref "R183") (pin "1") (pinfunction "1_1") (pintype "passive"))
    )
    (net (code "29") (name "/REF_CLK_IN") (class "Default")
      (node (ref "J36") (pin "2") (pinfunction "2_2") (pintype "passive"))
    )
    (net (code "30") (name "/RPI_PIN16") (class "Default")
      (node (ref "IC35") (pin "2") (pinfunction "D-_2") (pintype "passive"))
      (node (ref "R173") (pin "2") (pinfunction "2_2") (pintype "passive"))
    )
    (net (code "31") (name "/RPI_PIN18") (class "Default")
      (node (ref "IC35") (pin "1") (pinfunction "D+_1") (pintype "passive"))
      (node (ref "R171") (pin "2") (pinfunction "2_2") (pintype "passive"))
    )
    (net (code "32") (name "/RPI_SYNC_IN") (class "Default")
      (node (ref "IC4") (pin "4") (pinfunction "B_4") (pintype "bidirectional"))
      (node (ref "J38") (pin "2") (pinfunction "2_2") (pintype "passive"))
      (node (ref "R23") (pin "1") (pinfunction "1_1") (pintype "passive"))
    )
    (net (code "33") (name "/RPI_SYNC_IN_LS") (class "Default")
      (node (ref "IC35") (pin "4") (pinfunction "HSD1-_4") (pintype "passive"))
      (node (ref "IC35") (pin "7") (pinfunction "HSD2+_7") (pintype "passive"))
      (node (ref "IC4") (pin "3") (pinfunction "A_3") (pintype "bidirectional"))
      (node (ref "R173") (pin "1") (pinfunction "1_1") (pintype "passive"))
      (node (ref "R23") (pin "2") (pinfunction "2_2") (pintype "passive"))
    )
    (net (code "34") (name "/RPI_SYNC_OUT") (class "Default")
      (node (ref "IC2") (pin "4") (pinfunction "B_4") (pintype "bidirectional"))
      (node (ref "J58") (pin "3") (pinfunction "3_3") (pintype "passive"))
      (node (ref "R16") (pin "1") (pinfunction "1_1") (pintype "passive"))
    )
    (net (code "35") (name "/RPI_SYNC_OUT_LS") (class "Default")
      (node (ref "IC2") (pin "3") (pinfunction "A_3") (pintype "bidirectional"))
      (node (ref "IC35") (pin "5") (pinfunction "HSD1+_5") (pintype "passive"))
      (node (ref "R16") (pin "2") (pinfunction "2_2") (pintype "passive"))
      (node (ref "R171") (pin "1") (pinfunction "1_1") (pintype "passive"))
    )
    (net (code "36") (name "/SYNC_OUT") (class "Default")
      (node (ref "J34") (pin "2") (pinfunction "2_2") (pintype "passive"))
      (node (ref "J37") (pin "1") (pinfunction "1_1") (pintype "passive"))
      (node (ref "J58") (pin "2") (pinfunction "2_2") (pintype "passive"))
    )
    (net (code "37") (name "/XO10_VC") (class "Default")
      (node (ref "XO10") (pin "1") (pinfunction "Vcon_1") (pintype "passive"))
      (node (ref "XO6") (pin "1") (pinfunction "NC/VC_1") (pintype "passive"))
      (node (ref "XO7") (pin "1") (pinfunction "VC_1") (pintype "passive"))
      (node (ref "XO8") (pin "1") (pinfunction "Vc_1") (pintype "passive"))
      (node (ref "XO9") (pin "1") (pinfunction "VCO_1") (pintype "input"))
    )
    (net (code "38") (name "GND") (class "Default")
      (node (ref "C10") (pin "2") (pinfunction "2_2") (pintype "passive"))
      (node (ref "C11") (pin "2") (pinfunction "2_2") (pintype "passive"))
      (node (ref "C147") (pin "2") (pinfunction "2_2") (pintype "passive"))
      (node (ref "C16") (pin "2") (pinfunction "2_2") (pintype "passive"))
      (node (ref "C18") (pin "2") (pinfunction "2_2") (pintype "passive"))
      (node (ref "C272") (pin "1") (pinfunction "1_1") (pintype "passive"))
      (node (ref "C275") (pin "1") (pinfunction "1_1") (pintype "passive"))
      (node (ref "C276") (pin "1") (pinfunction "1_1") (pintype "passive"))
      (node (ref "C278") (pin "2") (pinfunction "2_2") (pintype "passive"))
      (node (ref "C279") (pin "2") (pinfunction "2_2") (pintype "passive"))
      (node (ref "C280") (pin "1") (pinfunction "1_1") (pintype "passive"))
      (node (ref "C281") (pin "2") (pinfunction "2_2") (pintype "passive"))
      (node (ref "C284") (pin "1") (pinfunction "1_1") (pintype "passive"))
      (node (ref "C285") (pin "1") (pinfunction "1_1") (pintype "passive"))
      (node (ref "C286") (pin "2") (pinfunction "2_2") (pintype "passive"))
      (node (ref "C289") (pin "1") (pinfunction "1_1") (pintype "passive"))
      (node (ref "C290") (pin "1") (pinfunction "1_1") (pintype "passive"))
      (node (ref "C291") (pin "1") (pinfunction "1_1") (pintype "passive"))
      (node (ref "C292") (pin "1") (pinfunction "1_1") (pintype "passive"))
      (node (ref "C293") (pin "1") (pinfunction "1_1") (pintype "passive"))
      (node (ref "C294") (pin "1") (pinfunction "1_1") (pintype "passive"))
      (node (ref "C295") (pin "1") (pinfunction "1_1") (pintype "passive"))
      (node (ref "C296") (pin "1") (pinfunction "1_1") (pintype "passive"))
      (node (ref "C297") (pin "1") (pinfunction "1_1") (pintype "passive"))
      (node (ref "C298") (pin "1") (pinfunction "1_1") (pintype "passive"))
      (node (ref "C299") (pin "1") (pinfunction "1_1") (pintype "passive"))
      (node (ref "C300") (pin "1") (pinfunction "1_1") (pintype "passive"))
      (node (ref "C301") (pin "1") (pinfunction "1_1") (pintype "passive"))
      (node (ref "C302") (pin "1") (pinfunction "1_1") (pintype "passive"))
      (node (ref "C303") (pin "1") (pinfunction "1_1") (pintype "passive"))
      (node (ref "C304") (pin "1") (pinfunction "1_1") (pintype "passive"))
      (node (ref "C305") (pin "1") (pinfunction "1_1") (pintype "passive"))
      (node (ref "C306") (pin "1") (pinfunction "1_1") (pintype "passive"))
      (node (ref "C307") (pin "1") (pinfunction "1_1") (pintype "passive"))
      (node (ref "C308") (pin "1") (pinfunction "1_1") (pintype "passive"))
      (node (ref "ESD38") (pin "2") (pinfunction "2_2") (pintype "passive"))
      (node (ref "IC2") (pin "2") (pinfunction "GND_2") (pintype "passive"))
      (node (ref "IC35") (pin "3") (pinfunction "GND_3") (pintype "passive"))
      (node (ref "IC35") (pin "8") (pinfunction "~{OE}_8") (pintype "input"))
      (node (ref "IC4") (pin "2") (pinfunction "GND_2") (pintype "passive"))
      (node (ref "IC4") (pin "5") (pinfunction "DIR_5") (pintype "input"))
      (node (ref "IC59") (pin "10") (pinfunction "GND_10") (pintype "passive"))
      (node (ref "IC59") (pin "12") (pinfunction "GND_12") (pintype "passive"))
      (node (ref "IC59") (pin "13") (pinfunction "GND_13") (pintype "passive"))
      (node (ref "IC59") (pin "24") (pinfunction "GND_24") (pintype "passive"))
      (node (ref "IC61") (pin "1") (pinfunction "GND_1") (pintype "passive"))
      (node (ref "IC61") (pin "11") (pinfunction "GND_11") (pintype "passive"))
      (node (ref "IC61") (pin "12") (pinfunction "GND_12") (pintype "passive"))
      (node (ref "IC61") (pin "16") (pinfunction "GND_16") (pintype "passive"))
      (node (ref "IC61") (pin "19") (pinfunction "GND_19") (pintype "passive"))
      (node (ref "IC61") (pin "22") (pinfunction "SEL_22") (pintype "passive"))
      (node (ref "IC61") (pin "25") (pinfunction "GND_25") (pintype "passive"))
      (node (ref "IC61") (pin "7") (pinfunction "GND_7") (pintype "passive"))
      (node (ref "IC62") (pin "2") (pinfunction "GND_2") (pintype "passive"))
      (node (ref "J32") (pin "2") (pinfunction "Y_2") (pintype "passive"))
      (node (ref "J35") (pin "2") (pinfunction "Y_2") (pintype "passive"))
      (node (ref "J55") (pin "1") (pinfunction "1_1") (pintype "passive"))
      (node (ref "J56") (pin "2") (pinfunction "Y_2") (pintype "passive"))
      (node (ref "J57") (pin "2") (pinfunction "Y_2") (pintype "passive"))
      (node (ref "R183") (pin "2") (pinfunction "2_2") (pintype "passive"))
      (node (ref "R294") (pin "1") (pinfunction "1_1") (pintype "passive"))
      (node (ref "R297") (pin "1") (pinfunction "1_1") (pintype "passive"))
      (node (ref "R301") (pin "1") (pinfunction "1_1") (pintype "passive"))
      (node (ref "R311") (pin "1") (pinfunction "1_1") (pintype "passive"))
      (node (ref "XO10") (pin "2") (pinfunction "GND_2") (pintype "passive"))
      (node (ref "XO6") (pin "2") (pinfunction "GND_2") (pintype "passive"))
      (node (ref "XO7") (pin "2") (pinfunction "GND_2") (pintype "passive"))
      (node (ref "XO8") (pin "2") (pinfunction "GND_2") (pintype "passive"))
      (node (ref "XO9") (pin "4") (pinfunction "GND_4") (pintype "passive"))
    )
    (net (code "39") (name "Net-(C272-Pad2)") (class "Default")
      (node (ref "C272") (pin "2") (pinfunction "2_2") (pintype "passive"))
      (node (ref "L11") (pin "2") (pinfunction "2_2") (pintype "passive"))
      (node (ref "R288") (pin "1") (pinfunction "1_1") (pintype "passive"))
    )
    (net (code "40") (name "Net-(C287-Pad2)") (class "Default")
      (node (ref "C287") (pin "2") (pinfunction "2_2") (pintype "passive"))
      (node (ref "C288") (pin "1") (pinfunction "1_1") (pintype "passive"))
      (node (ref "R311") (pin "2") (pinfunction "2_2") (pintype "passive"))
    )
    (net (code "41") (name "Net-(C288-Pad2)") (class "Default")
      (node (ref "C288") (pin "2") (pinfunction "2_2") (pintype "passive"))
      (node (ref "R308") (pin "1") (pinfunction "1_1") (pintype "passive"))
      (node (ref "R314") (pin "1") (pinfunction "1_1") (pintype "passive"))
      (node (ref "R317") (pin "2") (pinfunction "2_2") (pintype "passive"))
      (node (ref "R320") (pin "1") (pinfunction "1_1") (pintype "passive"))
    )
    (net (code "42") (name "Net-(FR17-Pad2)") (class "Default")
      (node (ref "FR17") (pin "2") (pinfunction "2_2") (pintype "passive"))
      (node (ref "R309") (pin "1") (pinfunction "1_1") (pintype "passive"))
      (node (ref "R315") (pin "2") (pinfunction "2_2") (pintype "passive"))
      (node (ref "R316") (pin "1") (pinfunction "1_1") (pintype "passive"))
      (node (ref "R319") (pin "1") (pinfunction "1_1") (pintype "passive"))
    )
    (net (code "43") (name "Net-(IC59-D_SEL)") (class "Default")
      (node (ref "IC59") (pin "2") (pinfunction "D_SEL_2") (pintype "passive"))
      (node (ref "R297") (pin "2") (pinfunction "2_2") (pintype "passive"))
    )
    (net (code "44") (name "Net-(IC59-RESET_N)") (class "Default")
      (node (ref "IC59") (pin "8") (pinfunction "RESET_N_8") (pintype "passive"))
      (node (ref "R293") (pin "2") (pinfunction "2_2") (pintype "passive"))
    )
    (net (code "45") (name "Net-(IC59-RF_IN)") (class "Default")
      (node (ref "C277") (pin "2") (pinfunction "2_2") (pintype "passive"))
      (node (ref "IC59") (pin "11") (pinfunction "RF_IN_11") (pintype "passive"))
    )
    (net (code "46") (name "Net-(IC59-SAFEBOOT_N)") (class "Default")
      (node (ref "IC59") (pin "1") (pinfunction "SAFEBOOT_N_1") (pintype "passive"))
      (node (ref "R301") (pin "2") (pinfunction "2_2") (pintype "passive"))
    )
    (net (code "47") (name "Net-(IC59-V_BCKP)") (class "Default")
      (node (ref "C279") (pin "1") (pinfunction "1_1") (pintype "passive"))
      (node (ref "IC59") (pin "22") (pinfunction "V_BCKP_22") (pintype "passive"))
      (node (ref "R299") (pin "1") (pinfunction "1_1") (pintype "passive"))
      (node (ref "R302") (pin "1") (pinfunction "1_1") (pintype "passive"))
    )
    (net (code "48") (name "Net-(IC61-CLKin)") (class "Default")
      (node (ref "C287") (pin "1") (pinfunction "1_1") (pintype "passive"))
      (node (ref "IC61") (pin "21") (pinfunction "CLKin_21") (pintype "passive"))
    )
    (net (code "49") (name "Net-(IC61-CLKin*)") (class "Default")
      (node (ref "C289") (pin "2") (pinfunction "2_2") (pintype "passive"))
      (node (ref "IC61") (pin "20") (pinfunction "CLKin*_20") (pintype "passive"))
    )
    (net (code "50") (name "Net-(IC61-OE)") (class "Default")
      (node (ref "IC61") (pin "24") (pinfunction "OE_24") (pintype "passive"))
      (node (ref "R310") (pin "1") (pinfunction "1_1") (pintype "passive"))
    )
    (net (code "51") (name "Net-(IC62-EN)") (class "Default")
      (node (ref "C305") (pin "2") (pinfunction "2_2") (pintype "passive"))
      (node (ref "C307") (pin "2") (pinfunction "2_2") (pintype "passive"))
      (node (ref "IC62") (pin "1") (pinfunction "IN_1") (pintype "input"))
      (node (ref "IC62") (pin "3") (pinfunction "EN_3") (pintype "input"))
      (node (ref "R319") (pin "2") (pinfunction "2_2") (pintype "passive"))
      (node (ref "R321") (pin "2") (pinfunction "2_2") (pintype "passive"))
    )
    (net (code "52") (name "Net-(IC62-OUT)") (class "Default")
      (node (ref "C306") (pin "2") (pinfunction "2_2") (pintype "passive"))
      (node (ref "C308") (pin "2") (pinfunction "2_2") (pintype "passive"))
      (node (ref "IC62") (pin "5") (pinfunction "OUT_5") (pintype "output"))
      (node (ref "R321") (pin "1") (pinfunction "1_1") (pintype "passive"))
      (node (ref "XO10") (pin "4") (pinfunction "VCC_4") (pintype "passive"))
    )
    (net (code "53") (name "Net-(J57-X)") (class "Default")
      (node (ref "J57") (pin "1") (pinfunction "X_1") (pintype "passive"))
      (node (ref "R312") (pin "1") (pinfunction "1_1") (pintype "passive"))
    )
    (net (code "54") (name "Net-(R285-Pad1)") (class "Default")
      (node (ref "R285") (pin "1") (pinfunction "1_1") (pintype "passive"))
      (node (ref "R286") (pin "2") (pinfunction "2_2") (pintype "passive"))
      (node (ref "R288") (pin "2") (pinfunction "2_2") (pintype "passive"))
    )
    (net (code "55") (name "Net-(R316-Pad2)") (class "Default")
      (node (ref "R316") (pin "2") (pinfunction "2_2") (pintype "passive"))
      (node (ref "R318") (pin "1") (pinfunction "1_1") (pintype "passive"))
    )
    (net (code "56") (name "Net-(XO6-Output)") (class "Default")
      (node (ref "R308") (pin "2") (pinfunction "2_2") (pintype "passive"))
      (node (ref "XO6") (pin "3") (pinfunction "Output_3") (pintype "output"))
    )
    (net (code "57") (name "Net-(XO6-Vcc)") (class "Default")
      (node (ref "C284") (pin "2") (pinfunction "2_2") (pintype "passive"))
      (node (ref "C285") (pin "2") (pinfunction "2_2") (pintype "passive"))
      (node (ref "C286") (pin "1") (pinfunction "1_1") (pintype "passive"))
      (node (ref "R309") (pin "2") (pinfunction "2_2") (pintype "passive"))
      (node (ref "XO6") (pin "4") (pinfunction "Vcc_4") (pintype "power_in"))
    )
    (net (code "58") (name "Net-(XO7-OUT)") (class "Default")
      (node (ref "R314") (pin "2") (pinfunction "2_2") (pintype "passive"))
      (node (ref "XO7") (pin "4") (pinfunction "OUT_4") (pintype "passive"))
      (node (ref "XO8") (pin "3") (pinfunction "OUT_3") (pintype "passive"))
    )
    (net (code "59") (name "Net-(XO7-TRI-ST.)") (class "Default")
      (node (ref "R313") (pin "1") (pinfunction "1_1") (pintype "passive"))
      (node (ref "XO7") (pin "6") (pinfunction "TRI-ST._6") (pintype "passive"))
    )
    (net (code "60") (name "Net-(XO7-VDD)") (class "Default")
      (node (ref "C290") (pin "2") (pinfunction "2_2") (pintype "passive"))
      (node (ref "C291") (pin "2") (pinfunction "2_2") (pintype "passive"))
      (node (ref "R313") (pin "2") (pinfunction "2_2") (pintype "passive"))
      (node (ref "R315") (pin "1") (pinfunction "1_1") (pintype "passive"))
      (node (ref "XO7") (pin "5") (pinfunction "VDD_5") (pintype "passive"))
      (node (ref "XO8") (pin "4") (pinfunction "VDD_4") (pintype "passive"))
    )
    (net (code "61") (name "Net-(XO9-RF_OUT)") (class "Default")
      (node (ref "R317") (pin "1") (pinfunction "1_1") (pintype "passive"))
      (node (ref "XO9") (pin "6") (pinfunction "RF_OUT_6") (pintype "output"))
    )
    (net (code "62") (name "Net-(XO9-VCC)") (class "Default")
      (node (ref "C296") (pin "2") (pinfunction "2_2") (pintype "passive"))
      (node (ref "C297") (pin "2") (pinfunction "2_2") (pintype "passive"))
      (node (ref "R318") (pin "2") (pinfunction "2_2") (pintype "passive"))
      (node (ref "XO9") (pin "9") (pinfunction "VCC_9") (pintype "power_in"))
    )
    (net (code "63") (name "Net-(XO9-VC_FILTER)") (class "Default")
      (node (ref "C298") (pin "2") (pinfunction "2_2") (pintype "passive"))
      (node (ref "XO9") (pin "7") (pinfunction "VC_FILTER_7") (pintype "input"))
    )
    (net (code "64") (name "Net-(XO10-OUT)") (class "Default")
      (node (ref "R320") (pin "2") (pinfunction "2_2") (pintype "passive"))
      (node (ref "XO10") (pin "3") (pinfunction "OUT_3") (pintype "passive"))
    )
    (net (code "65") (name "VCC3P0_BATT") (class "Default")
      (node (ref "J55") (pin "2") (pinfunction "2_2") (pintype "passive"))
      (node (ref "R299") (pin "2") (pinfunction "2_2") (pintype "passive"))
    )
    (net (code "66") (name "VCC3P3") (class "Default")
      (node (ref "C10") (pin "1") (pinfunction "1_1") (pintype "passive"))
      (node (ref "C11") (pin "1") (pinfunction "1_1") (pintype "passive"))
      (node (ref "C147") (pin "1") (pinfunction "1_1") (pintype "passive"))
      (node (ref "C16") (pin "1") (pinfunction "1_1") (pintype "passive"))
      (node (ref "C18") (pin "1") (pinfunction "1_1") (pintype "passive"))
      (node (ref "IC2") (pin "1") (pinfunction "VCCA_1") (pintype "power_in"))
      (node (ref "IC2") (pin "5") (pinfunction "DIR_5") (pintype "input"))
      (node (ref "IC2") (pin "6") (pinfunction "VCCB_6") (pintype "power_in"))
      (node (ref "IC35") (pin "9") (pinfunction "VCC_9") (pintype "power_in"))
      (node (ref "IC4") (pin "1") (pinfunction "VCCA_1") (pintype "power_in"))
      (node (ref "IC4") (pin "6") (pinfunction "VCCB_6") (pintype "power_in"))
      (node (ref "R292") (pin "1") (pinfunction "1_1") (pintype "passive"))
    )
    (net (code "67") (name "VCC3P3_CLK2") (class "Default")
      (node (ref "FR16") (pin "1") (pinfunction "1_1") (pintype "passive"))
      (node (ref "FR17") (pin "1") (pinfunction "1_1") (pintype "passive"))
      (node (ref "FR18") (pin "1") (pinfunction "1_1") (pintype "passive"))
      (node (ref "FR19") (pin "1") (pinfunction "1_1") (pintype "passive"))
    )
    (net (code "68") (name "VCC3P3_GNSS") (class "Default")
      (node (ref "C275") (pin "2") (pinfunction "2_2") (pintype "passive"))
      (node (ref "C276") (pin "2") (pinfunction "2_2") (pintype "passive"))
      (node (ref "C280") (pin "2") (pinfunction "2_2") (pintype "passive"))
      (node (ref "C281") (pin "1") (pinfunction "1_1") (pintype "passive"))
      (node (ref "FR16") (pin "2") (pinfunction "2_2") (pintype "passive"))
      (node (ref "IC59") (pin "23") (pinfunction "VCC_23") (pintype "passive"))
      (node (ref "R286") (pin "1") (pinfunction "1_1") (pintype "passive"))
      (node (ref "R302") (pin "2") (pinfunction "2_2") (pintype "passive"))
    )
    (net (code "69") (name "VCC3P3_LMK10") (class "Default")
      (node (ref "C292") (pin "2") (pinfunction "2_2") (pintype "passive"))
      (node (ref "C293") (pin "2") (pinfunction "2_2") (pintype "passive"))
      (node (ref "C294") (pin "2") (pinfunction "2_2") (pintype "passive"))
      (node (ref "C295") (pin "2") (pinfunction "2_2") (pintype "passive"))
      (node (ref "FR18") (pin "2") (pinfunction "2_2") (pintype "passive"))
      (node (ref "IC61") (pin "23") (pinfunction "Vdd_23") (pintype "passive"))
      (node (ref "IC61") (pin "8") (pinfunction "Vdd_8") (pintype "passive"))
      (node (ref "R310") (pin "2") (pinfunction "2_2") (pintype "passive"))
    )
    (net (code "70") (name "VCC3P3_LMK10_VDDO") (class "Default")
      (node (ref "C299") (pin "2") (pinfunction "2_2") (pintype "passive"))
      (node (ref "C300") (pin "2") (pinfunction "2_2") (pintype "passive"))
      (node (ref "C301") (pin "2") (pinfunction "2_2") (pintype "passive"))
      (node (ref "C302") (pin "2") (pinfunction "2_2") (pintype "passive"))
      (node (ref "C303") (pin "2") (pinfunction "2_2") (pintype "passive"))
      (node (ref "C304") (pin "2") (pinfunction "2_2") (pintype "passive"))
      (node (ref "FR19") (pin "2") (pinfunction "2_2") (pintype "passive"))
      (node (ref "IC61") (pin "14") (pinfunction "Vddo_14") (pintype "passive"))
      (node (ref "IC61") (pin "18") (pinfunction "Vddo_18") (pintype "passive"))
      (node (ref "IC61") (pin "2") (pinfunction "Vddo_2") (pintype "passive"))
      (node (ref "IC61") (pin "6") (pinfunction "Vddo_6") (pintype "passive"))
    )
    (net (code "71") (name "unconnected-(IC35-HSD2--Pad6)") (class "Default")
      (node (ref "IC35") (pin "6") (pinfunction "HSD2-_6") (pintype "passive+no_connect"))
    )
    (net (code "72") (name "unconnected-(IC59-GEOFENCE_STAT{slash}RESV-Pad16)") (class "Default")
      (node (ref "IC59") (pin "16") (pinfunction "GEOFENCE_STAT/RESV_16") (pintype "passive+no_connect"))
    )
    (net (code "73") (name "unconnected-(IC59-LNA_EN{slash}RESV-Pad14)") (class "Default")
      (node (ref "IC59") (pin "14") (pinfunction "LNA_EN/RESV_14") (pintype "passive+no_connect"))
    )
    (net (code "74") (name "unconnected-(IC59-RESV-Pad17)") (class "Default")
      (node (ref "IC59") (pin "17") (pinfunction "RESV_17") (pintype "passive+no_connect"))
    )
    (net (code "75") (name "unconnected-(IC59-RTK_STAT{slash}RESV-Pad15)") (class "Default")
      (node (ref "IC59") (pin "15") (pinfunction "RTK_STAT/RESV_15") (pintype "passive+no_connect"))
    )
    (net (code "76") (name "unconnected-(IC61-OSCin-Pad9)") (class "Default")
      (node (ref "IC61") (pin "9") (pinfunction "OSCin_9") (pintype "passive+no_connect"))
    )
    (net (code "77") (name "unconnected-(IC61-OSCout-Pad10)") (class "Default")
      (node (ref "IC61") (pin "10") (pinfunction "OSCout_10") (pintype "passive+no_connect"))
    )
    (net (code "78") (name "unconnected-(IC62-NC-Pad4)") (class "Default")
      (node (ref "IC62") (pin "4") (pinfunction "NC_4") (pintype "passive+no_connect"))
    )
    (net (code "79") (name "unconnected-(JMP2-Pad1)") (class "Default")
      (node (ref "JMP2") (pin "1") (pinfunction "1_1") (pintype "passive"))
    )
    (net (code "80") (name "unconnected-(JMP2-Pad2)") (class "Default")
      (node (ref "JMP2") (pin "2") (pinfunction "2_2") (pintype "passive"))
    )
    (net (code "81") (name "unconnected-(JMP3-Pad1)") (class "Default")
      (node (ref "JMP3") (pin "1") (pinfunction "1_1") (pintype "passive"))
    )
    (net (code "82") (name "unconnected-(JMP3-Pad2)") (class "Default")
      (node (ref "JMP3") (pin "2") (pinfunction "2_2") (pintype "passive"))
    )
    (net (code "83") (name "unconnected-(JMP4-Pad1)") (class "Default")
      (node (ref "JMP4") (pin "1") (pinfunction "1_1") (pintype "passive"))
    )
    (net (code "84") (name "unconnected-(JMP4-Pad2)") (class "Default")
      (node (ref "JMP4") (pin "2") (pinfunction "2_2") (pintype "passive"))
    )
    (net (code "85") (name "unconnected-(JMP5-Pad1)") (class "Default")
      (node (ref "JMP5") (pin "1") (pinfunction "1_1") (pintype "passive"))
    )
    (net (code "86") (name "unconnected-(JMP5-Pad2)") (class "Default")
      (node (ref "JMP5") (pin "2") (pinfunction "2_2") (pintype "passive"))
    )
    (net (code "87") (name "unconnected-(JMP6-Pad1)") (class "Default")
      (node (ref "JMP6") (pin "1") (pinfunction "1_1") (pintype "passive"))
    )
    (net (code "88") (name "unconnected-(JMP6-Pad2)") (class "Default")
      (node (ref "JMP6") (pin "2") (pinfunction "2_2") (pintype "passive"))
    )
    (net (code "89") (name "unconnected-(JMP8-Pad1)") (class "Default")
      (node (ref "JMP8") (pin "1") (pinfunction "1_1") (pintype "passive"))
    )
    (net (code "90") (name "unconnected-(JMP8-Pad2)") (class "Default")
      (node (ref "JMP8") (pin "2") (pinfunction "2_2") (pintype "passive"))
    )
    (net (code "91") (name "unconnected-(XO7-T.S.-Pad3)") (class "Default")
      (node (ref "XO7") (pin "3") (pinfunction "T.S._3") (pintype "passive+no_connect"))
    )
    (net (code "92") (name "unconnected-(XO9-NC-Pad2)") (class "Default")
      (node (ref "XO9") (pin "2") (pinfunction "NC_2") (pintype "passive+no_connect"))
    )
    (net (code "93") (name "unconnected-(XO9-NC-Pad3)") (class "Default")
      (node (ref "XO9") (pin "3") (pinfunction "NC_3") (pintype "passive+no_connect"))
    )
    (net (code "94") (name "unconnected-(XO9-NC-Pad5)") (class "Default")
      (node (ref "XO9") (pin "5") (pinfunction "NC_5") (pintype "passive+no_connect"))
    )
    (net (code "95") (name "unconnected-(XO9-NC-Pad8)") (class "Default")
      (node (ref "XO9") (pin "8") (pinfunction "NC_8") (pintype "passive+no_connect"))
    )
    (net (code "96") (name "unconnected-(XO9-NC-Pad10)") (class "Default")
      (node (ref "XO9") (pin "10") (pinfunction "NC_10") (pintype "passive+no_connect"))
    )
  )
)
